# CurrentSensor.net
KiCad netlist of a schematic drawn in Altium Designer
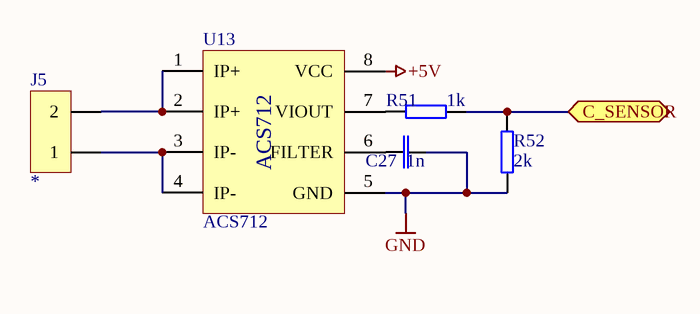
[diagram p0: CurrentSensor.SchDoc]

(export (version "E")
  (design (tool "Eeschema 10.0.6"))
  (components
    (comp (ref "C27")
      (value "1n")
      (footprint "CAP 0805")
      (description "NON POLARIZED CAPACITOR")
      (libsource (lib "SCH_LIB") (part "CAP"))
    )
    (comp (ref "J5")
      (value "*")
      (footprint "PTR_AKZ350")
      (description "2 PIN HEADER")
      (libsource (lib "SCH_LIB") (part "HEADER2"))
    )
    (comp (ref "R51")
      (value "1k")
      (footprint "RES 0805")
      (description "RESISTOR")
      (libsource (lib "") (part "RES_1"))
    )
    (comp (ref "R52")
      (value "2k")
      (footprint "RES 0805")
      (description "RESISTOR")
      (libsource (lib "SCH_LIB") (part "RES"))
    )
    (comp (ref "U13")
      (value "ACS712")
      (footprint "SO8")
      (description "Current sensor IC")
      (libsource (lib "SCH_LIB") (part "ACS712"))
    )
  )
  (nets
    (net (code "1") (name "+5V") (class "Default")
      (node (ref "U13") (pin "8") (pinfunction "VCC_8") (pintype "passive"))
    )
    (net (code "2") (name "/C_SENSOR") (class "Default")
      (node (ref "R51") (pin "1") (pinfunction "1_1") (pintype "passive"))
      (node (ref "R52") (pin "2") (pinfunction "2_2") (pintype "passive"))
    )
    (net (code "3") (name "GND") (class "Default")
      (node (ref "C27") (pin "1") (pinfunction "1_1") (pintype "passive"))
      (node (ref "R52") (pin "1") (pinfunction "1_1") (pintype "passive"))
      (node (ref "U13") (pin "5") (pinfunction "GND_5") (pintype "passive"))
    )
    (net (code "4") (name "Net-(J5-Pad1)") (class "Default")
      (node (ref "J5") (pin "1") (pinfunction "1_1") (pintype "passive"))
      (node (ref "U13") (pin "3") (pinfunction "IP-_3") (pintype "passive"))
      (node (ref "U13") (pin "4") (pinfunction "IP-_4") (pintype "passive"))
    )
    (net (code "5") (name "Net-(J5-Pad2)") (class "Default")
      (node (ref "J5") (pin "2") (pinfunction "2_2") (pintype "passive"))
      (node (ref "U13") (pin "1") (pinfunction "IP+_1") (pintype "passive"))
      (node (ref "U13") (pin "2") (pinfunction "IP+_2") (pintype "passive"))
    )
    (net (code "6") (name "Net-(U13-FILTER)") (class "Default")
      (node (ref "C27") (pin "2") (pinfunction "2_2") (pintype "passive"))
      (node (ref "U13") (pin "6") (pinfunction "FILTER_6") (pintype "passive"))
    )
    (net (code "7") (name "Net-(U13-VIOUT)") (class "Default")
      (node (ref "R51") (pin "2") (pinfunction "2_2") (pintype "passive"))
      (node (ref "U13") (pin "7") (pinfunction "VIOUT_7") (pintype "passive"))
    )
  )
)
